# NG2092_Power_Supply.net
KiCad netlist of a schematic drawn in Altium Designer
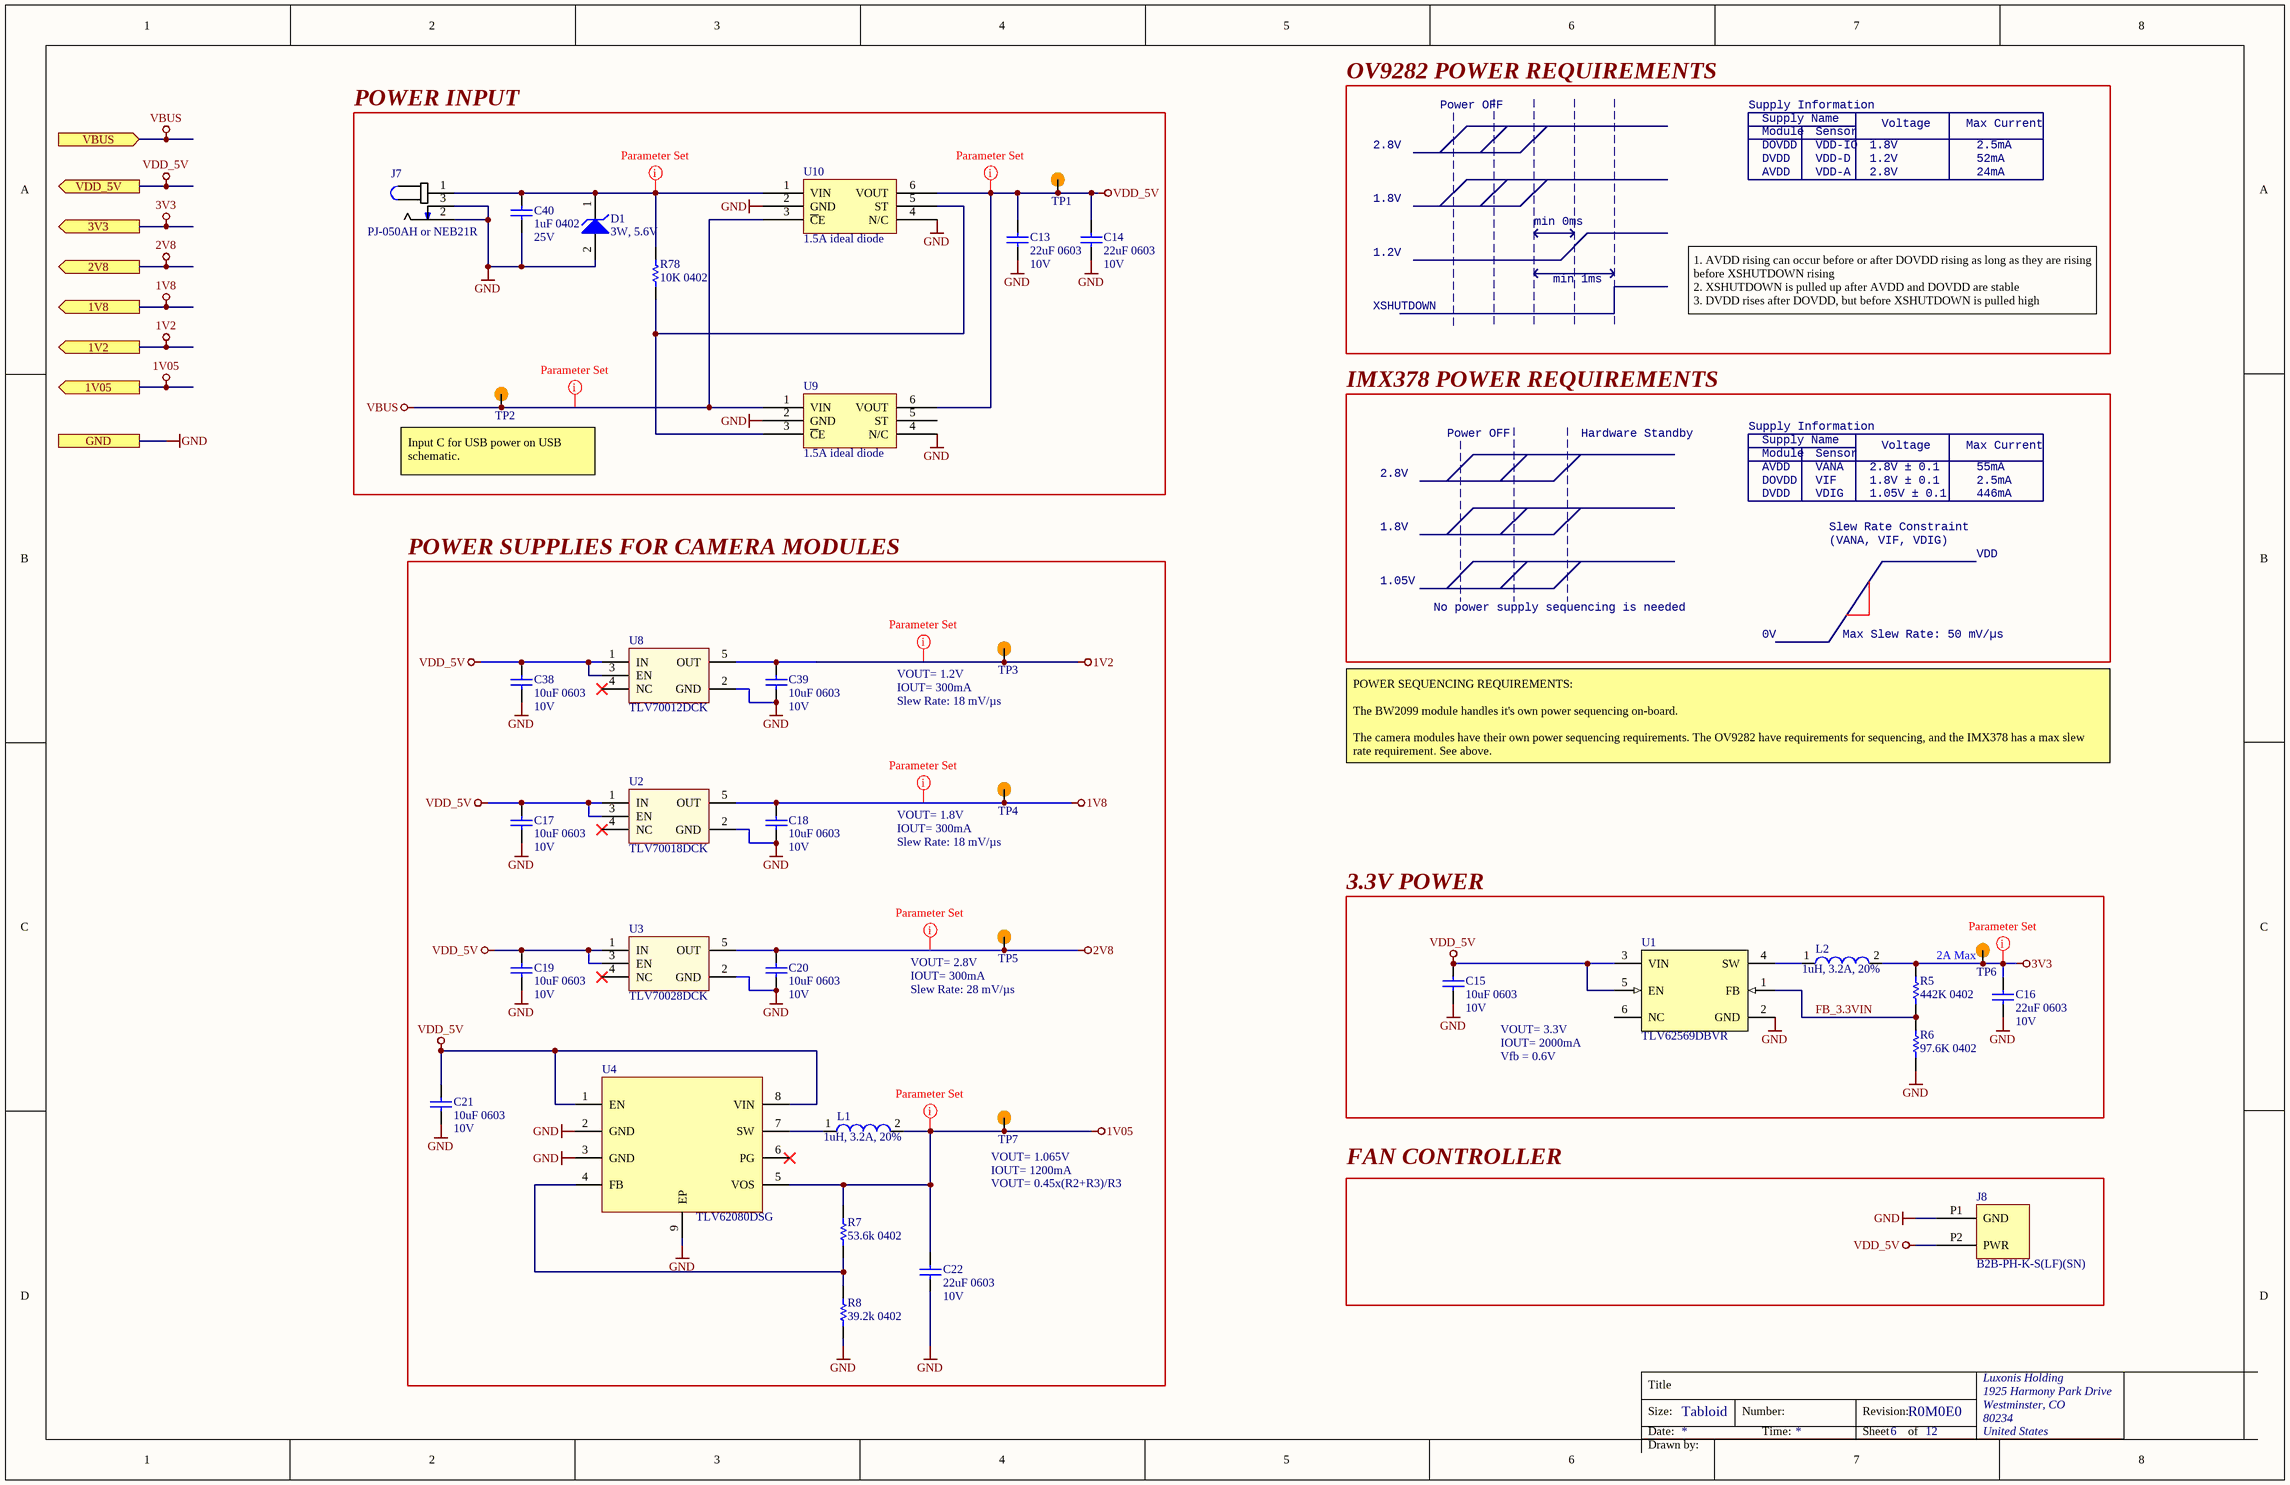
[diagram p0: NG2092_Power_Supply.SchDoc]

(export (version "E")
  (design (tool "Eeschema 10.0.6"))
  (components
    (comp (ref "C13")
      (value "22uF 0603")
      (footprint "CAP_Altium_Vault_Generic:CAPC0603(1608)100_L")
      (description "CAP CER 22UF 10V X5R 0603 20%")
      (fields (field (name "TOLERANCE") "20%") (field (name "VOLTAGE RATING") "10V"))
      (libsource (lib "LuxonisMaster") (part "GRM188R61A226ME15D"))
    )
    (comp (ref "C14")
      (value "22uF 0603")
      (footprint "CAP_Altium_Vault_Generic:CAPC0603(1608)100_L")
      (description "CAP CER 22UF 10V X5R 0603 20%")
      (fields (field (name "TOLERANCE") "20%") (field (name "VOLTAGE RATING") "10V"))
      (libsource (lib "LuxonisMaster") (part "GRM188R61A226ME15D"))
    )
    (comp (ref "C15")
      (value "10uF 0603")
      (footprint "CAP_Altium_Vault_Generic:CAPC0603(1608)100_L")
      (description "CAP CER 10UF 10V X5R 0603 20%")
      (fields (field (name "TOLERANCE") "20%") (field (name "VOLTAGE RATING") "10V"))
      (libsource (lib "LuxonisMaster") (part "GRM188R61A106ME69D"))
    )
    (comp (ref "C16")
      (value "22uF 0603")
      (footprint "CAP_Altium_Vault_Generic:CAPC0603(1608)100_L")
      (description "CAP CER 22UF 10V X5R 0603 20%")
      (fields (field (name "TOLERANCE") "20%") (field (name "VOLTAGE RATING") "10V"))
      (libsource (lib "LuxonisMaster") (part "GRM188R61A226ME15D"))
    )
    (comp (ref "C17")
      (value "10uF 0603")
      (footprint "CAP_Altium_Vault_Generic:CAPC0603(1608)100_L")
      (description "CAP CER 10UF 10V X5R 0603 20%")
      (fields (field (name "TOLERANCE") "20%") (field (name "VOLTAGE RATING") "10V"))
      (libsource (lib "LuxonisMaster") (part "GRM188R61A106ME69D"))
    )
    (comp (ref "C18")
      (value "10uF 0603")
      (footprint "CAP_Altium_Vault_Generic:CAPC0603(1608)100_L")
      (description "CAP CER 10UF 10V X5R 0603 20%")
      (fields (field (name "TOLERANCE") "20%") (field (name "VOLTAGE RATING") "10V"))
      (libsource (lib "LuxonisMaster") (part "GRM188R61A106ME69D"))
    )
    (comp (ref "C19")
      (value "10uF 0603")
      (footprint "CAP_Altium_Vault_Generic:CAPC0603(1608)100_L")
      (description "CAP CER 10UF 10V X5R 0603 20%")
      (fields (field (name "TOLERANCE") "20%") (field (name "VOLTAGE RATING") "10V"))
      (libsource (lib "LuxonisMaster") (part "GRM188R61A106ME69D"))
    )
    (comp (ref "C20")
      (value "10uF 0603")
      (footprint "CAP_Altium_Vault_Generic:CAPC0603(1608)100_L")
      (description "CAP CER 10UF 10V X5R 0603 20%")
      (fields (field (name "TOLERANCE") "20%") (field (name "VOLTAGE RATING") "10V"))
      (libsource (lib "LuxonisMaster") (part "GRM188R61A106ME69D"))
    )
    (comp (ref "C21")
      (value "10uF 0603")
      (footprint "CAP_Altium_Vault_Generic:CAPC0603(1608)100_L")
      (description "CAP CER 10UF 10V X5R 0603 20%")
      (fields (field (name "TOLERANCE") "20%") (field (name "VOLTAGE RATING") "10V"))
      (libsource (lib "LuxonisMaster") (part "GRM188R61A106ME69D"))
    )
    (comp (ref "C22")
      (value "22uF 0603")
      (footprint "CAP_Altium_Vault_Generic:CAPC0603(1608)100_L")
      (description "CAP CER 22UF 10V X5R 0603 20%")
      (fields (field (name "TOLERANCE") "20%") (field (name "VOLTAGE RATING") "10V"))
      (libsource (lib "LuxonisMaster") (part "GRM188R61A226ME15D"))
    )
    (comp (ref "C38")
      (value "10uF 0603")
      (footprint "CAP_Altium_Vault_Generic:CAPC0603(1608)100_L")
      (description "CAP CER 10UF 10V X5R 0603 20%")
      (fields (field (name "TOLERANCE") "20%") (field (name "VOLTAGE RATING") "10V"))
      (libsource (lib "LuxonisMaster") (part "GRM188R61A106ME69D"))
    )
    (comp (ref "C39")
      (value "10uF 0603")
      (footprint "CAP_Altium_Vault_Generic:CAPC0603(1608)100_L")
      (description "CAP CER 10UF 10V X5R 0603 20%")
      (fields (field (name "TOLERANCE") "20%") (field (name "VOLTAGE RATING") "10V"))
      (libsource (lib "LuxonisMaster") (part "GRM188R61A106ME69D"))
    )
    (comp (ref "C40")
      (value "1uF 0402")
      (footprint "CAP_Altium_Vault_Generic:CAPC0402(1005)70_N")
      (description "CAP CER 1UF 25V X5R 0402 10%")
      (fields
        (field (name "TOLERANCE") "10%")
        (field (name "VOLTAGE") "25V")
        (field (name "VOLTAGE RATING") "25V")
      )
      (libsource (lib "LuxonisMaster") (part "GRM155R61E105KA12D"))
    )
    (comp (ref "D1")
      (value "3W, 5.6V")
      (footprint "1SMB5919BT3G")
      (description "DIODE ZENER 5.6V 3W SMB")
      (fields (field (name "TOLERANCE") "5%"))
      (libsource (lib "NG2092") (part "1SMB5919BT3G"))
    )
    (comp (ref "J7")
      (value "PJ-050AH or NEB21R")
      (footprint "LuxonisMaster:PJ-050AH/NEB21R_COMBO")
      (description "CONN POWER PIN 2 POS RA PTH Barrel jack 2.1mm x 5.5mm combo footprint")
      (libsource (lib "LuxonisMaster") (part "PJ-050AH/NEB21R_COMBO"))
    )
    (comp (ref "J8")
      (value "B2B-PH-K-S(LF)(SN)")
      (footprint "LuxonisMaster:B2B-PH-K-S(LF)(SN)")
      (description "CONN HEADER VERT 2POS 2MM")
      (libsource (lib "LuxonisMaster") (part "B2B-PH-K-S(LF)(SN)"))
    )
    (comp (ref "L1")
      (value "1uH, 3.2A, 20%")
      (footprint "LuxonisMaster:DFE252012P-1R0M=P2")
      (description "FIXED IND 1UH 3.2A 42 MOHM SMD")
      (fields (field (name "TOLERANCE") "20%"))
      (libsource (lib "LuxonisMaster") (part "DFE252012P-1R0M=P2"))
    )
    (comp (ref "L2")
      (value "1uH, 3.2A, 20%")
      (footprint "LuxonisMaster:DFE252012P-1R0M=P2")
      (description "FIXED IND 1UH 3.2A 42 MOHM SMD")
      (fields (field (name "TOLERANCE") "20%"))
      (libsource (lib "LuxonisMaster") (part "DFE252012P-1R0M=P2"))
    )
    (comp (ref "R5")
      (value "442K 0402")
      (footprint "RES_Altium_Vault_Generic:RESC0402(1005)_N")
      (description "RES SMD 442K OHM 1% 1/16W 0402")
      (fields (field (name "TOLERANCE") "1%"))
      (libsource (lib "DM1092_R0M0E0") (part "CRCW0402442KFKED"))
    )
    (comp (ref "R6")
      (value "97.6K 0402")
      (footprint "RES_Altium_Vault_Generic:RESC0402(1005)_N")
      (description "RES SMD 97.6K OHM 1% 1/16W 0402")
      (fields (field (name "TOLERANCE") "1%"))
      (libsource (lib "DM1092_R0M0E0") (part "CRCW040297K6FKED"))
    )
    (comp (ref "R7")
      (value "53.6k 0402")
      (footprint "RES_Altium_Vault_Generic:RESC0402(1005)_L")
      (description "RES SMD 53.6K OHM 1% 1/16W 0402")
      (fields (field (name "TOLERANCE") "1%"))
      (libsource (lib "LuxonisMaster") (part "CRCW040253K6FKED"))
    )
    (comp (ref "R8")
      (value "39.2k 0402")
      (footprint "RES_Altium_Vault_Generic:RESC0402(1005)_L")
      (description "RES SMD 39.2K OHM 1% 1/16W 0402")
      (fields (field (name "TOLERANCE") "1%"))
      (libsource (lib "LuxonisMaster") (part "CRCW040239K2FKED"))
    )
    (comp (ref "R78")
      (value "10K 0402")
      (footprint "RES_Altium_Vault_Generic:RESC0402(1005)_N")
      (fields (field (name "TOLERANCE") "1%"))
      (libsource (lib "LuxonisMaster") (part "RC0402FR-1310KL"))
    )
    (comp (ref "TP1")
      (value "TP075_150_NS")
      (footprint "LuxonisMaster:TP075_150_NS")
      (libsource (lib "LuxonisMaster") (part "TEST_POINT"))
    )
    (comp (ref "TP2")
      (value "TP075_150_NS")
      (footprint "LuxonisMaster:TP075_150_NS")
      (libsource (lib "LuxonisMaster") (part "TEST_POINT"))
    )
    (comp (ref "TP3")
      (value "TP075_150_NS")
      (footprint "LuxonisMaster:TP075_150_NS")
      (libsource (lib "LuxonisMaster") (part "TEST_POINT"))
    )
    (comp (ref "TP4")
      (value "TP075_150_NS")
      (footprint "LuxonisMaster:TP075_150_NS")
      (libsource (lib "LuxonisMaster") (part "TEST_POINT"))
    )
    (comp (ref "TP5")
      (value "TP075_150_NS")
      (footprint "LuxonisMaster:TP075_150_NS")
      (libsource (lib "LuxonisMaster") (part "TEST_POINT"))
    )
    (comp (ref "TP6")
      (value "TP075_150_NS")
      (footprint "LuxonisMaster:TP075_150_NS")
      (libsource (lib "LuxonisMaster") (part "TEST_POINT"))
    )
    (comp (ref "TP7")
      (value "TP075_150_NS")
      (footprint "LuxonisMaster:TP075_150_NS")
      (libsource (lib "LuxonisMaster") (part "TEST_POINT"))
    )
    (comp (ref "U1")
      (value "TLV62569DBVR")
      (footprint "SOT95P270X130-6N")
      (description "Switching Regulator, 2A, 1500kHz Switching Freq-Max, PDSO5")
      (libsource (lib "NG2092") (part "TLV62569DBVR"))
    )
    (comp (ref "U2")
      (value "TLV70018DCK")
      (footprint "LuxonisMaster:TLV70018DCK")
      (description "IC REG LINEAR 1.8V 200MA SC70-5 Linear Voltage Regulator IC  1 Output  200mA SC-70-5")
      (libsource (lib "LuxonisMaster") (part "TLV70018DCK"))
    )
    (comp (ref "U3")
      (value "TLV70028DCK")
      (footprint "LuxonisMaster:TLV70028DCK")
      (description "IC REG LINEAR 2.8V 200MA SC70-5 Linear Voltage Regulator IC  1 Output  200mA SC-70-5")
      (libsource (lib "LuxonisMaster") (part "TLV70028DCK"))
    )
    (comp (ref "U4")
      (value "TLV62080DSG")
      (footprint "LuxonisMaster:TLV62080DSG")
      (description "IC REG BUCK ADJ 1.2A SYNC 8WSON")
      (libsource (lib "LuxonisMaster") (part "TLV62080DSG"))
    )
    (comp (ref "U8")
      (value "TLV70012DCK")
      (footprint "LuxonisMaster:TLV70012DCK")
      (description "IC REG LINEAR 1.2V 200MA SC70-5")
      (libsource (lib "LuxonisMaster") (part "TLV70012DCK"))
    )
    (comp (ref "U9")
      (value "1.5A ideal diode")
      (footprint "LM66100DCKR")
      (description "IC OR CTRLR IDEAL DIODE SC70-6")
      (libsource (lib "NG2092") (part "LM66100DCKR"))
    )
    (comp (ref "U10")
      (value "1.5A ideal diode")
      (footprint "LM66100DCKR")
      (description "IC OR CTRLR IDEAL DIODE SC70-6")
      (libsource (lib "NG2092") (part "LM66100DCKR"))
    )
  )
  (nets
    (net (code "1") (name "/FB_3.3VIN") (class "Default")
      (node (ref "R5") (pin "1") (pinfunction "1_1") (pintype "passive"))
      (node (ref "R6") (pin "2") (pinfunction "2_2") (pintype "passive"))
      (node (ref "U1") (pin "1") (pinfunction "FB_1") (pintype "input"))
    )
    (net (code "2") (name "1V2") (class "Default")
      (node (ref "C39") (pin "2") (pinfunction "2_2") (pintype "passive"))
      (node (ref "TP3") (pin "1") (pintype "passive"))
      (node (ref "U8") (pin "5") (pinfunction "OUT_5") (pintype "passive"))
    )
    (net (code "3") (name "1V05") (class "Default")
      (node (ref "C22") (pin "2") (pinfunction "2_2") (pintype "passive"))
      (node (ref "L1") (pin "2") (pinfunction "2_2") (pintype "passive"))
      (node (ref "R7") (pin "2") (pinfunction "2_2") (pintype "passive"))
      (node (ref "TP7") (pin "1") (pintype "passive"))
      (node (ref "U4") (pin "5") (pinfunction "VOS_5") (pintype "passive"))
    )
    (net (code "4") (name "1V8") (class "Default")
      (node (ref "C18") (pin "2") (pinfunction "2_2") (pintype "passive"))
      (node (ref "TP4") (pin "1") (pintype "passive"))
      (node (ref "U2") (pin "5") (pinfunction "OUT_5") (pintype "passive"))
    )
    (net (code "5") (name "2V8") (class "Default")
      (node (ref "C20") (pin "2") (pinfunction "2_2") (pintype "passive"))
      (node (ref "TP5") (pin "1") (pintype "passive"))
      (node (ref "U3") (pin "5") (pinfunction "OUT_5") (pintype "passive"))
    )
    (net (code "6") (name "3V3") (class "Default")
      (node (ref "C16") (pin "1") (pinfunction "1_1") (pintype "passive"))
      (node (ref "L2") (pin "2") (pinfunction "2_2") (pintype "passive"))
      (node (ref "R5") (pin "2") (pinfunction "2_2") (pintype "passive"))
      (node (ref "TP6") (pin "1") (pintype "passive"))
    )
    (net (code "7") (name "GND") (class "Default")
      (node (ref "C13") (pin "1") (pinfunction "1_1") (pintype "passive"))
      (node (ref "C14") (pin "1") (pinfunction "1_1") (pintype "passive"))
      (node (ref "C15") (pin "1") (pinfunction "1_1") (pintype "passive"))
      (node (ref "C16") (pin "2") (pinfunction "2_2") (pintype "passive"))
      (node (ref "C17") (pin "1") (pinfunction "1_1") (pintype "passive"))
      (node (ref "C18") (pin "1") (pinfunction "1_1") (pintype "passive"))
      (node (ref "C19") (pin "1") (pinfunction "1_1") (pintype "passive"))
      (node (ref "C20") (pin "1") (pinfunction "1_1") (pintype "passive"))
      (node (ref "C21") (pin "1") (pinfunction "1_1") (pintype "passive"))
      (node (ref "C22") (pin "1") (pinfunction "1_1") (pintype "passive"))
      (node (ref "C38") (pin "1") (pinfunction "1_1") (pintype "passive"))
      (node (ref "C39") (pin "1") (pinfunction "1_1") (pintype "passive"))
      (node (ref "C40") (pin "1") (pinfunction "1_1") (pintype "passive"))
      (node (ref "D1") (pin "2") (pinfunction "A_2") (pintype "passive"))
      (node (ref "J7") (pin "2") (pinfunction "2_2") (pintype "passive"))
      (node (ref "J7") (pin "3") (pinfunction "3_3") (pintype "passive"))
      (node (ref "J8") (pin "P1") (pinfunction "GND_P1") (pintype "passive"))
      (node (ref "R6") (pin "1") (pinfunction "1_1") (pintype "passive"))
      (node (ref "R8") (pin "1") (pinfunction "1_1") (pintype "passive"))
      (node (ref "U1") (pin "2") (pinfunction "GND_2") (pintype "power_in"))
      (node (ref "U10") (pin "2") (pinfunction "GND_2") (pintype "passive"))
      (node (ref "U10") (pin "4") (pinfunction "N/C_4") (pintype "passive"))
      (node (ref "U2") (pin "2") (pinfunction "GND_2") (pintype "passive"))
      (node (ref "U3") (pin "2") (pinfunction "GND_2") (pintype "passive"))
      (node (ref "U4") (pin "2") (pinfunction "GND_2") (pintype "passive"))
      (node (ref "U4") (pin "3") (pinfunction "GND_3") (pintype "passive"))
      (node (ref "U4") (pin "9") (pinfunction "EP_9") (pintype "passive"))
      (node (ref "U8") (pin "2") (pinfunction "GND_2") (pintype "passive"))
      (node (ref "U9") (pin "2") (pinfunction "GND_2") (pintype "passive"))
      (node (ref "U9") (pin "4") (pinfunction "N/C_4") (pintype "passive"))
    )
    (net (code "8") (name "Net-(D1-K)") (class "Default")
      (node (ref "C40") (pin "2") (pinfunction "2_2") (pintype "passive"))
      (node (ref "D1") (pin "1") (pinfunction "K_1") (pintype "passive"))
      (node (ref "J7") (pin "1") (pinfunction "1_1") (pintype "passive"))
      (node (ref "R78") (pin "2") (pinfunction "2_2") (pintype "passive"))
      (node (ref "U10") (pin "1") (pinfunction "VIN_1") (pintype "passive"))
    )
    (net (code "9") (name "Net-(U1-SW)") (class "Default")
      (node (ref "L2") (pin "1") (pinfunction "1_1") (pintype "passive"))
      (node (ref "U1") (pin "4") (pinfunction "SW_4") (pintype "power_in"))
    )
    (net (code "10") (name "Net-(U4-FB)") (class "Default")
      (node (ref "R7") (pin "1") (pinfunction "1_1") (pintype "passive"))
      (node (ref "R8") (pin "2") (pinfunction "2_2") (pintype "passive"))
      (node (ref "U4") (pin "4") (pinfunction "FB_4") (pintype "passive"))
    )
    (net (code "11") (name "Net-(U4-SW)") (class "Default")
      (node (ref "L1") (pin "1") (pinfunction "1_1") (pintype "passive"))
      (node (ref "U4") (pin "7") (pinfunction "SW_7") (pintype "passive"))
    )
    (net (code "12") (name "Net-(U10-ST)") (class "Default")
      (node (ref "R78") (pin "1") (pinfunction "1_1") (pintype "passive"))
      (node (ref "U10") (pin "5") (pinfunction "ST_5") (pintype "passive"))
      (node (ref "U9") (pin "3") (pinfunction "~{C}E_3") (pintype "passive"))
    )
    (net (code "13") (name "VBUS") (class "Default")
      (node (ref "TP2") (pin "1") (pintype "passive"))
      (node (ref "U10") (pin "3") (pinfunction "~{C}E_3") (pintype "passive"))
      (node (ref "U9") (pin "1") (pinfunction "VIN_1") (pintype "passive"))
    )
    (net (code "14") (name "VDD_5V") (class "Default")
      (node (ref "C13") (pin "2") (pinfunction "2_2") (pintype "passive"))
      (node (ref "C14") (pin "2") (pinfunction "2_2") (pintype "passive"))
      (node (ref "C15") (pin "2") (pinfunction "2_2") (pintype "passive"))
      (node (ref "C17") (pin "2") (pinfunction "2_2") (pintype "passive"))
      (node (ref "C19") (pin "2") (pinfunction "2_2") (pintype "passive"))
      (node (ref "C21") (pin "2") (pinfunction "2_2") (pintype "passive"))
      (node (ref "C38") (pin "2") (pinfunction "2_2") (pintype "passive"))
      (node (ref "J8") (pin "P2") (pinfunction "PWR_P2") (pintype "passive"))
      (node (ref "TP1") (pin "1") (pintype "passive"))
      (node (ref "U1") (pin "3") (pinfunction "VIN_3") (pintype "power_in"))
      (node (ref "U1") (pin "5") (pinfunction "EN_5") (pintype "input"))
      (node (ref "U10") (pin "6") (pinfunction "VOUT_6") (pintype "passive"))
      (node (ref "U2") (pin "1") (pinfunction "IN_1") (pintype "passive"))
      (node (ref "U2") (pin "3") (pinfunction "EN_3") (pintype "passive"))
      (node (ref "U3") (pin "1") (pinfunction "IN_1") (pintype "passive"))
      (node (ref "U3") (pin "3") (pinfunction "EN_3") (pintype "passive"))
      (node (ref "U4") (pin "1") (pinfunction "EN_1") (pintype "passive"))
      (node (ref "U4") (pin "8") (pinfunction "VIN_8") (pintype "passive"))
      (node (ref "U8") (pin "1") (pinfunction "IN_1") (pintype "passive"))
      (node (ref "U8") (pin "3") (pinfunction "EN_3") (pintype "passive"))
      (node (ref "U9") (pin "6") (pinfunction "VOUT_6") (pintype "passive"))
    )
    (net (code "15") (name "unconnected-(U1-NC-Pad6)") (class "Default")
      (node (ref "U1") (pin "6") (pinfunction "NC_6") (pintype "passive"))
    )
    (net (code "16") (name "unconnected-(U2-NC-Pad4)") (class "Default")
      (node (ref "U2") (pin "4") (pinfunction "NC_4") (pintype "passive+no_connect"))
    )
    (net (code "17") (name "unconnected-(U3-NC-Pad4)") (class "Default")
      (node (ref "U3") (pin "4") (pinfunction "NC_4") (pintype "passive+no_connect"))
    )
    (net (code "18") (name "unconnected-(U4-PG-Pad6)") (class "Default")
      (node (ref "U4") (pin "6") (pinfunction "PG_6") (pintype "passive+no_connect"))
    )
    (net (code "19") (name "unconnected-(U8-NC-Pad4)") (class "Default")
      (node (ref "U8") (pin "4") (pinfunction "NC_4") (pintype "passive+no_connect"))
    )
    (net (code "20") (name "unconnected-(U9-ST-Pad5)") (class "Default")
      (node (ref "U9") (pin "5") (pinfunction "ST_5") (pintype "passive"))
    )
  )
)
